# pruebaTension.net
KiCad netlist of a schematic drawn in EAGLE
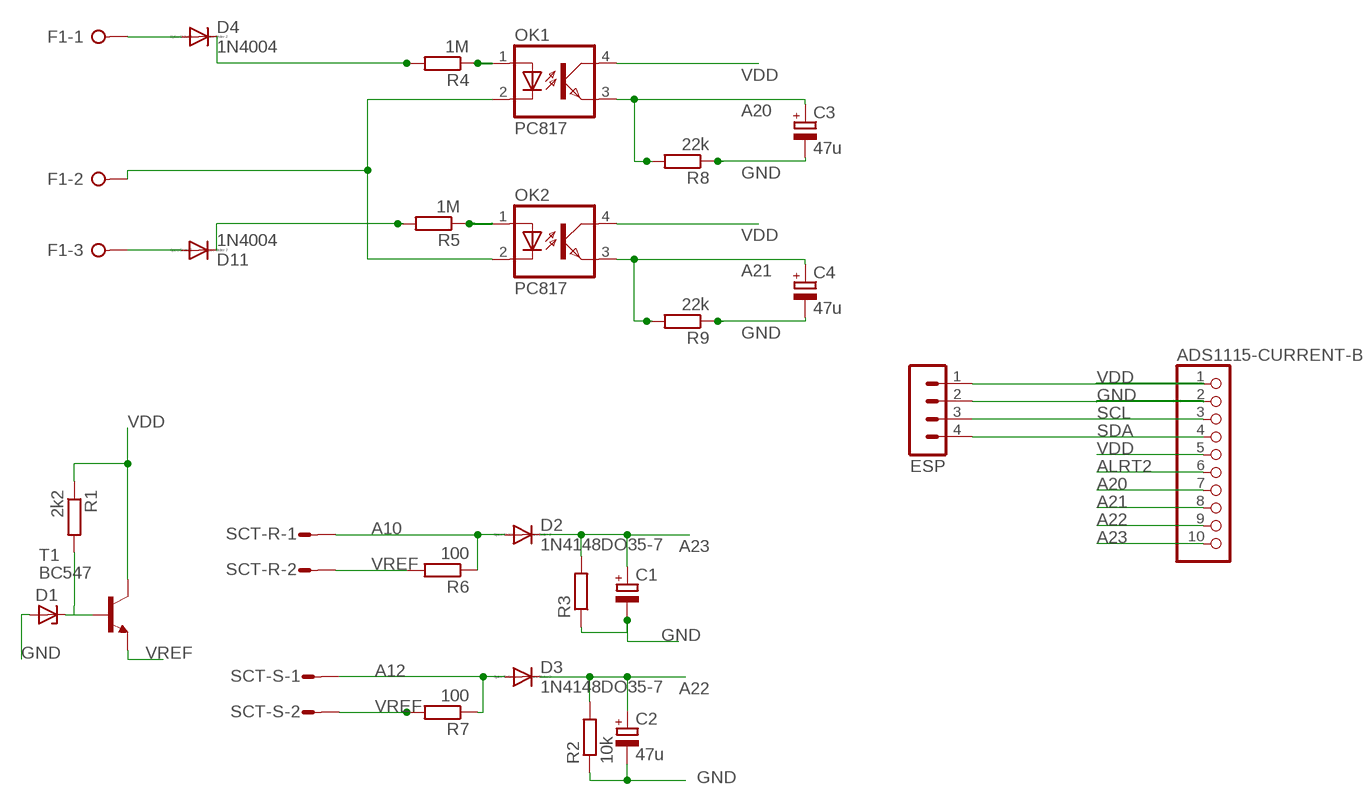
[diagram p0: schematic, sheet 1]

(export (version "E")
  (design (tool "Eeschema 10.0.6"))
  (components
    (comp (ref "ADS1115-CURRENT-B")
      (value "PINHD-1X10")
      (footprint "eagle-import:1X10")
      (libsource (lib "eagle-import") (part "PINHD-1X10"))
    )
    (comp (ref "C1")
      (value "CPOL-EUE2.5-7")
      (footprint "eagle-import:E2,5-7")
      (libsource (lib "eagle-import") (part "CPOL-EUE2.5-7"))
    )
    (comp (ref "C2")
      (value "47u")
      (footprint "eagle-import:E2,5-7")
      (libsource (lib "eagle-import") (part "CPOL-EUE2.5-7"))
    )
    (comp (ref "C3")
      (value "47u")
      (footprint "eagle-import:E2,5-7")
      (libsource (lib "eagle-import") (part "CPOL-EUE2.5-7"))
    )
    (comp (ref "C4")
      (value "47u")
      (footprint "eagle-import:E2,5-7")
      (libsource (lib "eagle-import") (part "CPOL-EUE2.5-7"))
    )
    (comp (ref "D1")
      (value "ZENER-DIODEZD-2.5")
      (footprint "eagle-import:ZDIO-2.5")
      (libsource (lib "eagle-import") (part "ZENER-DIODEZD-2.5"))
    )
    (comp (ref "D2")
      (value "1N4148DO35-7")
      (footprint "eagle-import:DO35-7")
      (libsource (lib "eagle-import") (part "1N4148DO35-7"))
    )
    (comp (ref "D3")
      (value "1N4148DO35-7")
      (footprint "eagle-import:DO35-7")
      (libsource (lib "eagle-import") (part "1N4148DO35-7"))
    )
    (comp (ref "D4")
      (value "1N4004")
      (footprint "eagle-import:DO41-10")
      (libsource (lib "eagle-import") (part "1N4004"))
    )
    (comp (ref "D11")
      (value "1N4004")
      (footprint "eagle-import:DO41-10")
      (libsource (lib "eagle-import") (part "1N4004"))
    )
    (comp (ref "ESP")
      (value "MA04-1")
      (footprint "eagle-import:MA04-1")
      (libsource (lib "eagle-import") (part "MA04-1"))
    )
    (comp (ref "F1")
      (value "W237-3E")
      (footprint "eagle-import:W237-3E")
      (libsource (lib "eagle-import") (part "W237-3E"))
    )
    (comp (ref "OK1")
      (value "PC817")
      (footprint "eagle-import:DIL04")
      (fields (field (name "MPN") "PC817X4J000F"))
      (libsource (lib "eagle-import") (part "PC817"))
    )
    (comp (ref "OK2")
      (value "PC817")
      (footprint "eagle-import:DIL04")
      (fields (field (name "MPN") "PC817X4J000F"))
      (libsource (lib "eagle-import") (part "PC817"))
    )
    (comp (ref "R1")
      (value "2k2")
      (footprint "eagle-import:0204V")
      (libsource (lib "eagle-import") (part "R-EU_0204/2V"))
    )
    (comp (ref "R2")
      (value "10k")
      (footprint "eagle-import:0204V")
      (libsource (lib "eagle-import") (part "R-EU_0204/2V"))
    )
    (comp (ref "R3")
      (value "R-EU_0204/2V")
      (footprint "eagle-import:0204V")
      (libsource (lib "eagle-import") (part "R-EU_0204/2V"))
    )
    (comp (ref "R4")
      (value "1M")
      (footprint "eagle-import:0204V")
      (libsource (lib "eagle-import") (part "R-EU_0204/2V"))
    )
    (comp (ref "R5")
      (value "1M")
      (footprint "eagle-import:0204V")
      (libsource (lib "eagle-import") (part "R-EU_0204/2V"))
    )
    (comp (ref "R6")
      (value "100")
      (footprint "eagle-import:0204V")
      (libsource (lib "eagle-import") (part "R-EU_0204/2V"))
    )
    (comp (ref "R7")
      (value "100")
      (footprint "eagle-import:0204V")
      (libsource (lib "eagle-import") (part "R-EU_0204/2V"))
    )
    (comp (ref "R8")
      (value "22k")
      (footprint "eagle-import:0204V")
      (libsource (lib "eagle-import") (part "R-EU_0204/2V"))
    )
    (comp (ref "R9")
      (value "22k")
      (footprint "eagle-import:0204V")
      (libsource (lib "eagle-import") (part "R-EU_0204/2V"))
    )
    (comp (ref "SCT-R")
      (value "S02P")
      (footprint "eagle-import:S02P")
      (libsource (lib "eagle-import") (part "S02P"))
    )
    (comp (ref "SCT-S")
      (value "S02P")
      (footprint "eagle-import:S02P")
      (libsource (lib "eagle-import") (part "S02P"))
    )
    (comp (ref "T1")
      (value "BC547")
      (footprint "eagle-import:TO92")
      (libsource (lib "eagle-import") (part "BC547"))
    )
  )
  (nets
    (net (code "1") (name "/A10") (class "Default")
      (node (ref "D2") (pin "A") (pinfunction "A_A") (pintype "passive"))
      (node (ref "R6") (pin "1") (pinfunction "1_1") (pintype "passive"))
      (node (ref "SCT-R") (pin "1") (pinfunction "S_1") (pintype "passive"))
    )
    (net (code "2") (name "/A12") (class "Default")
      (node (ref "D3") (pin "A") (pinfunction "A_A") (pintype "passive"))
      (node (ref "R7") (pin "1") (pinfunction "1_1") (pintype "passive"))
      (node (ref "SCT-S") (pin "1") (pinfunction "S_1") (pintype "passive"))
    )
    (net (code "3") (name "/A20") (class "Default")
      (node (ref "ADS1115-CURRENT-B") (pin "7") (pinfunction "7_7") (pintype "passive"))
      (node (ref "C3") (pin "+") (pinfunction "+_+") (pintype "passive"))
      (node (ref "OK1") (pin "3") (pinfunction "EMIT_3") (pintype "passive"))
      (node (ref "R8") (pin "2") (pinfunction "2_2") (pintype "passive"))
    )
    (net (code "4") (name "/A21") (class "Default")
      (node (ref "ADS1115-CURRENT-B") (pin "8") (pinfunction "8_8") (pintype "passive"))
      (node (ref "C4") (pin "+") (pinfunction "+_+") (pintype "passive"))
      (node (ref "OK2") (pin "3") (pinfunction "EMIT_3") (pintype "passive"))
      (node (ref "R9") (pin "2") (pinfunction "2_2") (pintype "passive"))
    )
    (net (code "5") (name "/A22") (class "Default")
      (node (ref "ADS1115-CURRENT-B") (pin "9") (pinfunction "9_9") (pintype "passive"))
      (node (ref "C2") (pin "+") (pinfunction "+_+") (pintype "passive"))
      (node (ref "D3") (pin "C") (pinfunction "C_C") (pintype "passive"))
      (node (ref "R2") (pin "2") (pinfunction "2_2") (pintype "passive"))
    )
    (net (code "6") (name "/A23") (class "Default")
      (node (ref "ADS1115-CURRENT-B") (pin "10") (pinfunction "10_10") (pintype "passive"))
      (node (ref "C1") (pin "+") (pinfunction "+_+") (pintype "passive"))
      (node (ref "D2") (pin "C") (pinfunction "C_C") (pintype "passive"))
      (node (ref "R3") (pin "2") (pinfunction "2_2") (pintype "passive"))
    )
    (net (code "7") (name "/ALRT2") (class "Default")
      (node (ref "ADS1115-CURRENT-B") (pin "6") (pinfunction "6_6") (pintype "passive"))
    )
    (net (code "8") (name "/GND") (class "Default")
      (node (ref "ADS1115-CURRENT-B") (pin "2") (pinfunction "2_2") (pintype "passive"))
      (node (ref "C1") (pin "-") (pinfunction "-_-") (pintype "passive"))
      (node (ref "C2") (pin "-") (pinfunction "-_-") (pintype "passive"))
      (node (ref "C3") (pin "-") (pinfunction "-_-") (pintype "passive"))
      (node (ref "C4") (pin "-") (pinfunction "-_-") (pintype "passive"))
      (node (ref "D1") (pin "A") (pinfunction "A_A") (pintype "passive"))
      (node (ref "ESP") (pin "2") (pinfunction "2_2") (pintype "passive"))
      (node (ref "R2") (pin "1") (pinfunction "1_1") (pintype "passive"))
      (node (ref "R3") (pin "1") (pinfunction "1_1") (pintype "passive"))
      (node (ref "R8") (pin "1") (pinfunction "1_1") (pintype "passive"))
      (node (ref "R9") (pin "1") (pinfunction "1_1") (pintype "passive"))
    )
    (net (code "9") (name "/SCL") (class "Default")
      (node (ref "ADS1115-CURRENT-B") (pin "3") (pinfunction "3_3") (pintype "passive"))
      (node (ref "ESP") (pin "3") (pinfunction "3_3") (pintype "passive"))
    )
    (net (code "10") (name "/SDA") (class "Default")
      (node (ref "ADS1115-CURRENT-B") (pin "4") (pinfunction "4_4") (pintype "passive"))
      (node (ref "ESP") (pin "4") (pinfunction "4_4") (pintype "passive"))
    )
    (net (code "11") (name "/VDD") (class "Default")
      (node (ref "ADS1115-CURRENT-B") (pin "1") (pinfunction "1_1") (pintype "passive"))
      (node (ref "ADS1115-CURRENT-B") (pin "5") (pinfunction "5_5") (pintype "passive"))
      (node (ref "ESP") (pin "1") (pinfunction "1_1") (pintype "passive"))
      (node (ref "OK1") (pin "4") (pinfunction "COL_4") (pintype "passive"))
      (node (ref "OK2") (pin "4") (pinfunction "COL_4") (pintype "passive"))
      (node (ref "R1") (pin "1") (pinfunction "1_1") (pintype "passive"))
      (node (ref "T1") (pin "3") (pinfunction "C_3") (pintype "passive"))
    )
    (net (code "12") (name "/VREF") (class "Default")
      (node (ref "R6") (pin "2") (pinfunction "2_2") (pintype "passive"))
      (node (ref "R7") (pin "2") (pinfunction "2_2") (pintype "passive"))
      (node (ref "SCT-R") (pin "2") (pinfunction "S_2") (pintype "passive"))
      (node (ref "SCT-S") (pin "2") (pinfunction "S_2") (pintype "passive"))
      (node (ref "T1") (pin "1") (pinfunction "E_1") (pintype "passive"))
    )
    (net (code "13") (name "Net-(D4-PadC)") (class "Default")
      (node (ref "D4") (pin "C") (pinfunction "C_C") (pintype "passive"))
      (node (ref "R4") (pin "2") (pinfunction "2_2") (pintype "passive"))
    )
    (net (code "14") (name "Net-(D11-PadC)") (class "Default")
      (node (ref "D11") (pin "C") (pinfunction "C_C") (pintype "passive"))
      (node (ref "R5") (pin "2") (pinfunction "2_2") (pintype "passive"))
    )
    (net (code "15") (name "Net-(F1A-KL)") (class "Default")
      (node (ref "D4") (pin "A") (pinfunction "A_A") (pintype "passive"))
      (node (ref "F1") (pin "1") (pinfunction "KL_1") (pintype "passive"))
    )
    (net (code "16") (name "Net-(F1B-KL)") (class "Default")
      (node (ref "F1") (pin "2") (pinfunction "KL_2") (pintype "passive"))
      (node (ref "OK1") (pin "2") (pinfunction "C_2") (pintype "passive"))
      (node (ref "OK2") (pin "2") (pinfunction "C_2") (pintype "passive"))
    )
    (net (code "17") (name "Net-(F1C-KL)") (class "Default")
      (node (ref "D11") (pin "A") (pinfunction "A_A") (pintype "passive"))
      (node (ref "F1") (pin "3") (pinfunction "KL_3") (pintype "passive"))
    )
    (net (code "18") (name "Net-(OK1-A)") (class "Default")
      (node (ref "OK1") (pin "1") (pinfunction "A_1") (pintype "passive"))
      (node (ref "R4") (pin "1") (pinfunction "1_1") (pintype "passive"))
    )
    (net (code "19") (name "Net-(OK2-A)") (class "Default")
      (node (ref "OK2") (pin "1") (pinfunction "A_1") (pintype "passive"))
      (node (ref "R5") (pin "1") (pinfunction "1_1") (pintype "passive"))
    )
    (net (code "20") (name "Net-(T1-B)") (class "Default")
      (node (ref "D1") (pin "C") (pinfunction "C_C") (pintype "passive"))
      (node (ref "R1") (pin "2") (pinfunction "2_2") (pintype "passive"))
      (node (ref "T1") (pin "2") (pinfunction "B_2") (pintype "passive"))
    )
  )
)
